# GoodNightLight.net
KiCad netlist of a schematic drawn in EAGLE
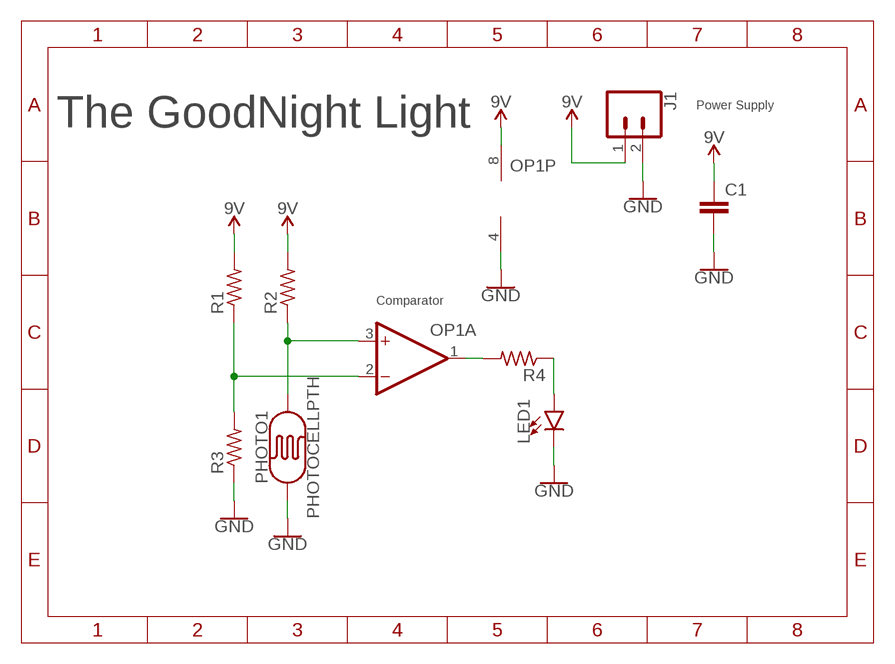
[diagram p0: schematic, sheet 1]

(export (version "E")
  (design (tool "Eeschema 10.0.6"))
  (components
    (comp (ref "C1")
      (value "CAPACITOR0603")
      (footprint "eagle-import:C0603")
      (libsource (lib "eagle-import") (part "CAPACITOR0603"))
    )
    (comp (ref "J1")
      (value "CONN_02")
      (footprint "eagle-import:1X02")
      (libsource (lib "eagle-import") (part "CONN_02"))
    )
    (comp (ref "LED1")
      (value "LED5MM")
      (footprint "eagle-import:LED_5MM")
      (libsource (lib "eagle-import") (part "LED5MM"))
    )
    (comp (ref "OP1")
      (value "OP-DUALR")
      (footprint "eagle-import:SO8")
      (fields (field (name "MPN") "AD8607ARMZ-R2"))
      (libsource (lib "eagle-import") (part "OP-DUALR"))
    )
    (comp (ref "PHOTO1")
      (value "PHOTOCELLPTH")
      (footprint "eagle-import:PHOTOCELL")
      (libsource (lib "eagle-import") (part "PHOTOCELLPTH"))
    )
    (comp (ref "R1")
      (value "RESISTOR0603")
      (footprint "eagle-import:R0603")
      (libsource (lib "eagle-import") (part "RESISTOR0603"))
    )
    (comp (ref "R2")
      (value "RESISTOR0603")
      (footprint "eagle-import:R0603")
      (libsource (lib "eagle-import") (part "RESISTOR0603"))
    )
    (comp (ref "R3")
      (value "RESISTOR0603")
      (footprint "eagle-import:R0603")
      (libsource (lib "eagle-import") (part "RESISTOR0603"))
    )
    (comp (ref "R4")
      (value "RESISTOR0603")
      (footprint "eagle-import:R0603")
      (libsource (lib "eagle-import") (part "RESISTOR0603"))
    )
  )
  (nets
    (net (code "1") (name "9V") (class "Default")
      (node (ref "C1") (pin "1") (pinfunction "1_1") (pintype "passive"))
      (node (ref "J1") (pin "1") (pinfunction "1_1") (pintype "passive"))
      (node (ref "OP1") (pin "8") (pinfunction "V+_8") (pintype "power_in"))
      (node (ref "R1") (pin "2") (pinfunction "2_2") (pintype "passive"))
      (node (ref "R2") (pin "2") (pinfunction "2_2") (pintype "passive"))
    )
    (net (code "2") (name "GND") (class "Default")
      (node (ref "C1") (pin "2") (pinfunction "2_2") (pintype "passive"))
      (node (ref "J1") (pin "2") (pinfunction "2_2") (pintype "passive"))
      (node (ref "LED1") (pin "K") (pinfunction "C_K") (pintype "passive"))
      (node (ref "OP1") (pin "4") (pinfunction "V-_4") (pintype "power_in"))
      (node (ref "PHOTO1") (pin "1") (pinfunction "P$1_1") (pintype "bidirectional"))
      (node (ref "R3") (pin "1") (pinfunction "1_1") (pintype "passive"))
    )
    (net (code "3") (name "Net-(LED1-PadA)") (class "Default")
      (node (ref "LED1") (pin "A") (pinfunction "A_A") (pintype "passive"))
      (node (ref "R4") (pin "1") (pinfunction "1_1") (pintype "passive"))
    )
    (net (code "4") (name "Net-(OP1A-+IN)") (class "Default")
      (node (ref "OP1") (pin "3") (pinfunction "+IN_3") (pintype "input"))
      (node (ref "PHOTO1") (pin "2") (pinfunction "P$2_2") (pintype "bidirectional"))
      (node (ref "R2") (pin "1") (pinfunction "1_1") (pintype "passive"))
    )
    (net (code "5") (name "Net-(OP1A--IN)") (class "Default")
      (node (ref "OP1") (pin "2") (pinfunction "-IN_2") (pintype "input"))
      (node (ref "R1") (pin "1") (pinfunction "1_1") (pintype "passive"))
      (node (ref "R3") (pin "2") (pinfunction "2_2") (pintype "passive"))
    )
    (net (code "6") (name "Net-(OP1A-OUT)") (class "Default")
      (node (ref "OP1") (pin "1") (pinfunction "OUT_1") (pintype "output"))
      (node (ref "R4") (pin "2") (pinfunction "2_2") (pintype "passive"))
    )
  )
)
